# MCU021_V1_0_eZFET_DCDC.net
KiCad netlist of a schematic drawn in Altium Designer
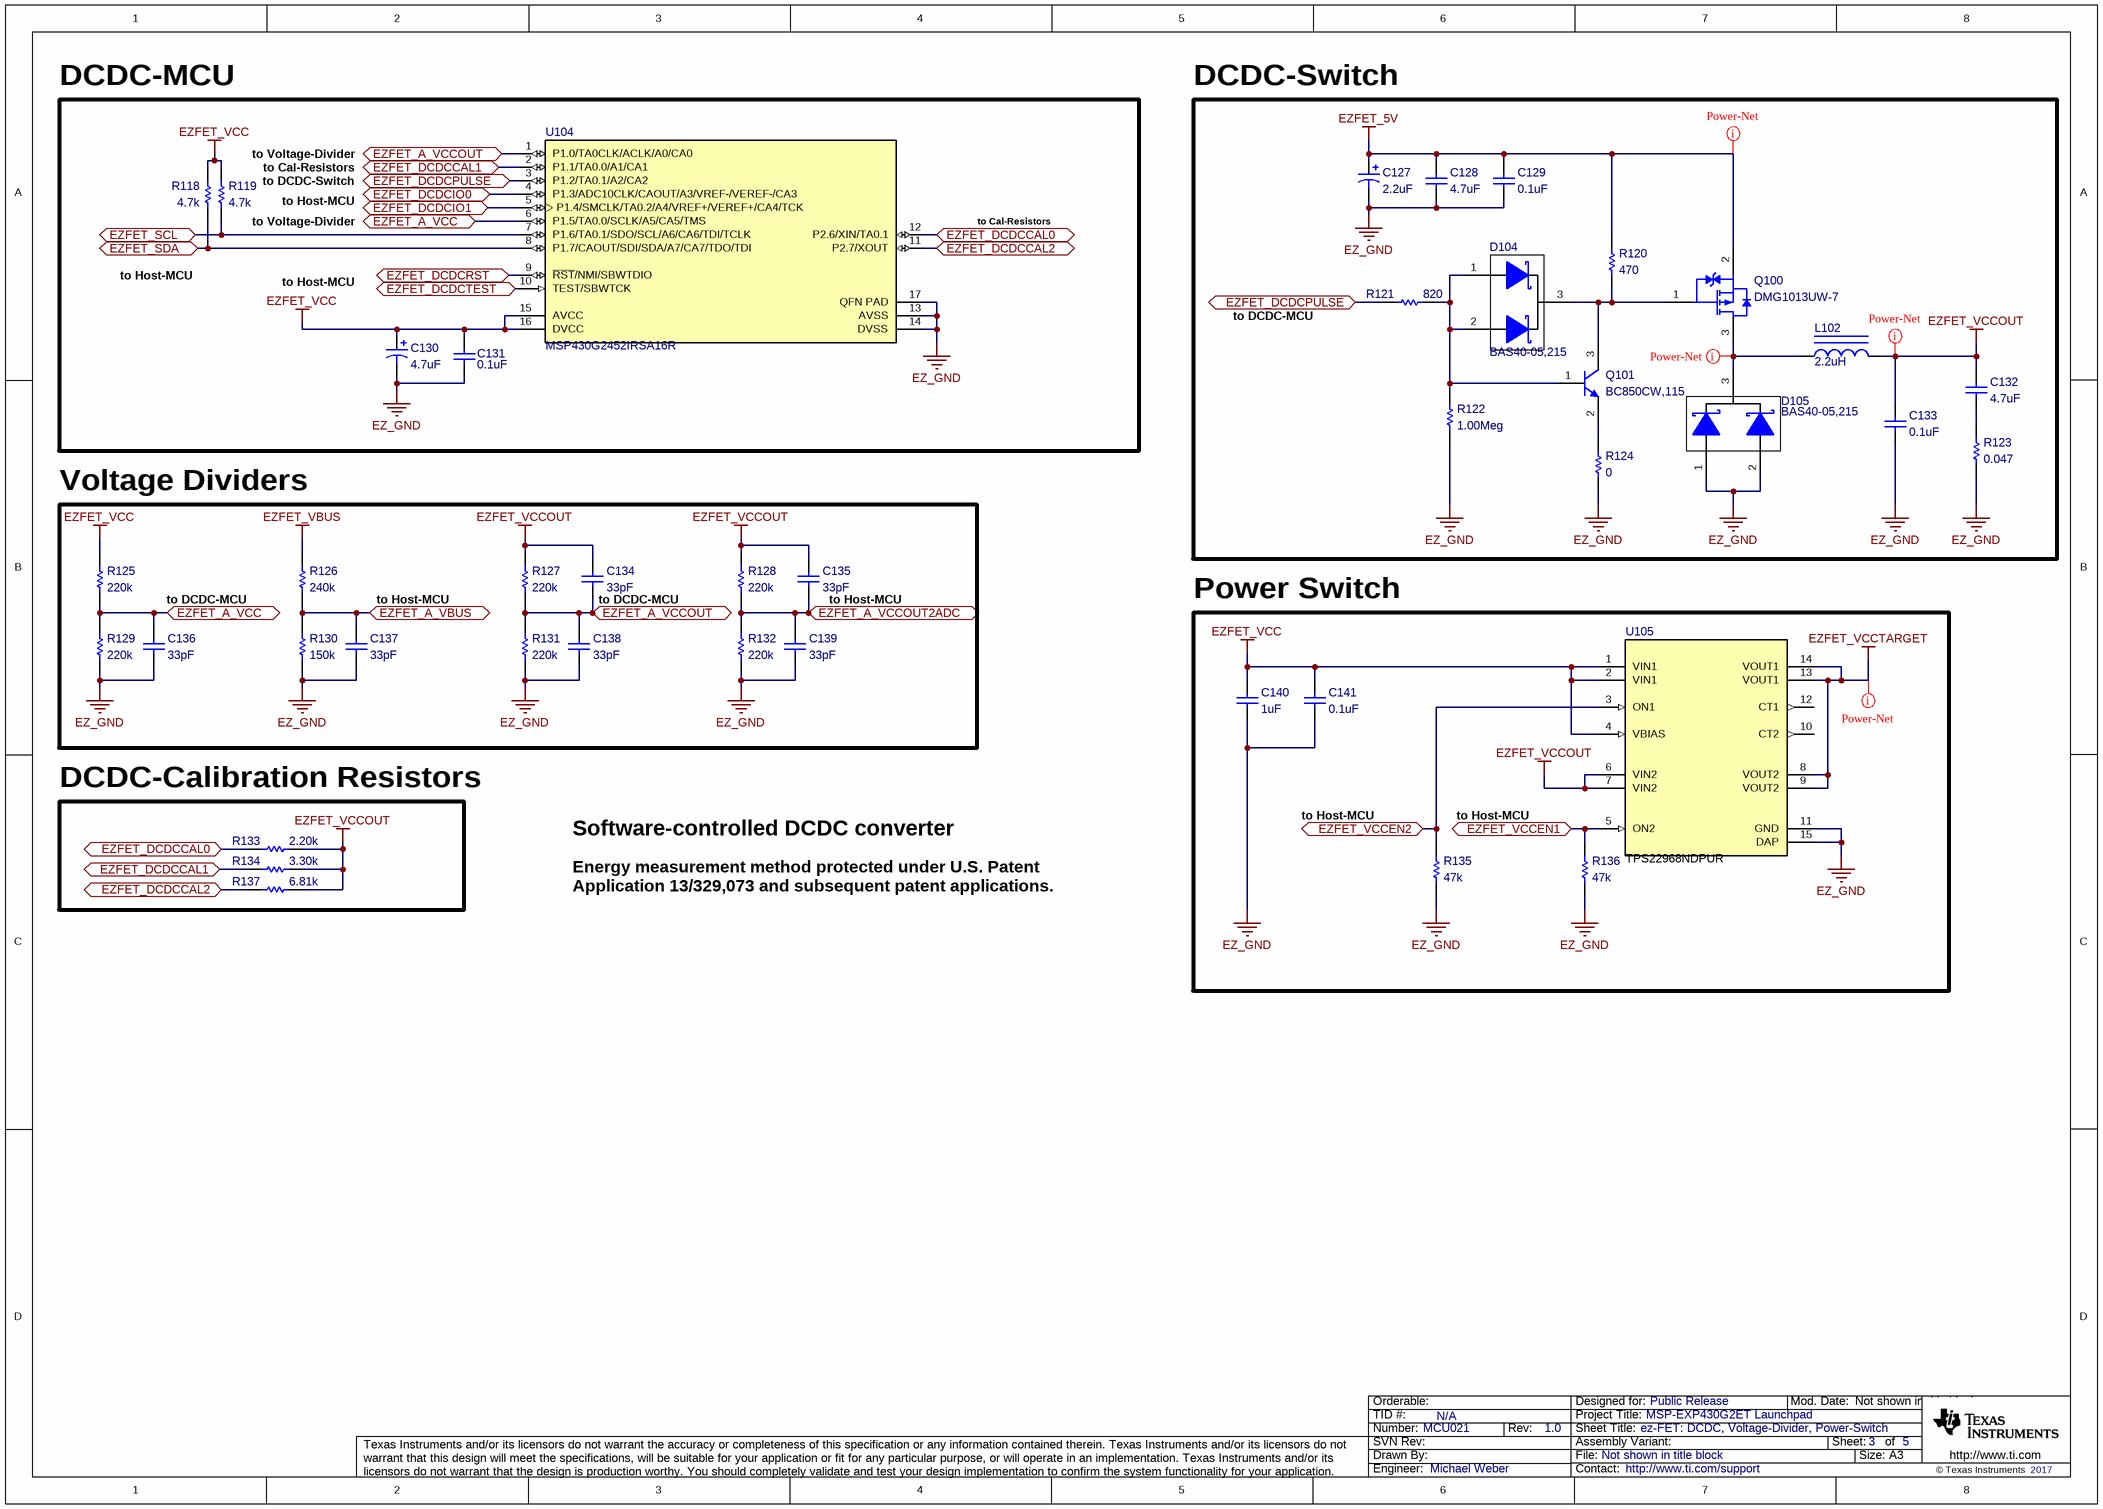
[diagram p0: MCU021_V1.0_eZFET_DCDC.SchDoc]

(export (version "E")
  (design (tool "Eeschema 10.0.6"))
  (components
    (comp (ref "C127")
      (value "2.2uF")
      (footprint "3216-18")
      (description "CAP, TA, 2.2 µF, 25 V, +/- 10%, 6.3 ohm, SMD")
      (fields
        (field (name "PARTNUMBER") "293D225X9025A2TE3")
        (field (name "MANUFACTURER") "Vishay-Sprague")
        (field (name "PUBLISHER") "Texas Instruments")
      )
      (libsource (lib "Capacitor_Tantalum") (part "293D225X9025A2TE3"))
    )
    (comp (ref "C128")
      (value "4.7uF")
      (footprint "0805_HV")
      (description "CAP, CERM, 4.7 µF, 10 V,+/- 10%, X5R, 0805")
      (fields
        (field (name "PARTNUMBER") "C0805C475K8PACTU")
        (field (name "MANUFACTURER") "Kemet")
        (field (name "PUBLISHER") "Texas Instruments")
      )
      (libsource (lib "Capacitor_Ceramic") (part "C0805C475K8PACTU"))
    )
    (comp (ref "C129")
      (value "0.1uF")
      (footprint "0402")
      (description "CAP, CERM, 0.1 µF, 10 V,+/- 10%, X5R, 0402")
      (fields
        (field (name "PARTNUMBER") "GRM155R61A104KA01D")
        (field (name "MANUFACTURER") "MuRata")
        (field (name "PUBLISHER") "Texas Instruments")
      )
      (libsource (lib "Capacitor_Ceramic") (part "GRM155R61A104KA01D"))
    )
    (comp (ref "C130")
      (value "4.7uF")
      (footprint "3216-18")
      (description "CAP, TA, 4.7 µF, 10 V, +/- 10%, 5 ohm, SMD")
      (fields
        (field (name "PARTNUMBER") "293D475X9010A2TE3")
        (field (name "MANUFACTURER") "Vishay-Sprague")
        (field (name "PUBLISHER") "Texas Instruments")
      )
      (libsource (lib "Capacitor_Tantalum") (part "293D475X9010A2TE3"))
    )
    (comp (ref "C131")
      (value "0.1uF")
      (footprint "0402")
      (description "CAP, CERM, 0.1 µF, 10 V,+/- 10%, X5R, 0402")
      (fields
        (field (name "PARTNUMBER") "GRM155R61A104KA01D")
        (field (name "MANUFACTURER") "MuRata")
        (field (name "PUBLISHER") "Texas Instruments")
      )
      (libsource (lib "Capacitor_Ceramic") (part "GRM155R61A104KA01D"))
    )
    (comp (ref "C132")
      (value "4.7uF")
      (footprint "0603")
      (description "CAP, CERM, 4.7 µF, 10 V,+/- 10%, X5R, 0603")
      (fields
        (field (name "PARTNUMBER") "CGB3B1X5R1A475K055AC")
        (field (name "MANUFACTURER") "TDK")
        (field (name "PUBLISHER") "Texas Instruments")
      )
      (libsource (lib "Capacitor_Ceramic") (part "CGB3B1X5R1A475K055AC"))
    )
    (comp (ref "C133")
      (value "0.1uF")
      (footprint "0402")
      (description "CAP, CERM, 0.1 µF, 10 V,+/- 10%, X5R, 0402")
      (fields
        (field (name "PARTNUMBER") "C1005X5R1A104K050BA")
        (field (name "MANUFACTURER") "TDK")
        (field (name "PUBLISHER") "Texas Instruments")
      )
      (libsource (lib "Capacitor_Ceramic") (part "C1005X5R1A104K050BA"))
    )
    (comp (ref "C134")
      (value "33pF")
      (footprint "0402")
      (description "CAP, CERM, 33 pF, 50 V,+/- 5%, C0G/NP0, 0402")
      (fields
        (field (name "PARTNUMBER") "C1005C0G1H330J050BA")
        (field (name "MANUFACTURER") "TDK")
        (field (name "PUBLISHER") "Texas Instruments")
      )
      (libsource (lib "Capacitor_Ceramic") (part "C1005C0G1H330J050BA"))
    )
    (comp (ref "C135")
      (value "33pF")
      (footprint "0402")
      (description "CAP, CERM, 33 pF, 50 V,+/- 5%, C0G/NP0, 0402")
      (fields
        (field (name "PARTNUMBER") "C1005C0G1H330J050BA")
        (field (name "MANUFACTURER") "TDK")
        (field (name "PUBLISHER") "Texas Instruments")
      )
      (libsource (lib "Capacitor_Ceramic") (part "C1005C0G1H330J050BA"))
    )
    (comp (ref "C136")
      (value "33pF")
      (footprint "0402")
      (description "CAP, CERM, 33 pF, 50 V,+/- 5%, C0G/NP0, 0402")
      (fields
        (field (name "PARTNUMBER") "C1005C0G1H330J050BA")
        (field (name "MANUFACTURER") "TDK")
        (field (name "PUBLISHER") "Texas Instruments")
      )
      (libsource (lib "Capacitor_Ceramic") (part "C1005C0G1H330J050BA"))
    )
    (comp (ref "C137")
      (value "33pF")
      (footprint "0402")
      (description "CAP, CERM, 33 pF, 50 V,+/- 5%, C0G/NP0, 0402")
      (fields
        (field (name "PARTNUMBER") "C1005C0G1H330J050BA")
        (field (name "MANUFACTURER") "TDK")
        (field (name "PUBLISHER") "Texas Instruments")
      )
      (libsource (lib "Capacitor_Ceramic") (part "C1005C0G1H330J050BA"))
    )
    (comp (ref "C138")
      (value "33pF")
      (footprint "0402")
      (description "CAP, CERM, 33 pF, 50 V,+/- 5%, C0G/NP0, 0402")
      (fields
        (field (name "PARTNUMBER") "C1005C0G1H330J050BA")
        (field (name "MANUFACTURER") "TDK")
        (field (name "PUBLISHER") "Texas Instruments")
      )
      (libsource (lib "Capacitor_Ceramic") (part "C1005C0G1H330J050BA"))
    )
    (comp (ref "C139")
      (value "33pF")
      (footprint "0402")
      (description "CAP, CERM, 33 pF, 50 V,+/- 5%, C0G/NP0, 0402")
      (fields
        (field (name "PARTNUMBER") "C1005C0G1H330J050BA")
        (field (name "MANUFACTURER") "TDK")
        (field (name "PUBLISHER") "Texas Instruments")
      )
      (libsource (lib "Capacitor_Ceramic") (part "C1005C0G1H330J050BA"))
    )
    (comp (ref "C140")
      (value "1uF")
      (footprint "0402")
      (description "CAP, CERM, 1 µF, 10 V,+/- 10%, X5R, 0402")
      (fields
        (field (name "PARTNUMBER") "GRM155R61A105KE15D")
        (field (name "MANUFACTURER") "MuRata")
        (field (name "PUBLISHER") "Texas Instruments")
      )
      (libsource (lib "Capacitor_Ceramic") (part "GRM155R61A105KE15D"))
    )
    (comp (ref "C141")
      (value "0.1uF")
      (footprint "0402")
      (description "CAP, CERM, 0.1 µF, 10 V,+/- 10%, X5R, 0402")
      (fields
        (field (name "PARTNUMBER") "GRM155R61A104KA01D")
        (field (name "MANUFACTURER") "MuRata")
        (field (name "PUBLISHER") "Texas Instruments")
      )
      (libsource (lib "Capacitor_Ceramic") (part "GRM155R61A104KA01D"))
    )
    (comp (ref "D104")
      (value "BAS40-05,215")
      (footprint "SOT-23")
      (description "Diode, Schottky, 40 V, 0.12 A, AEC-Q101, SOT-23")
      (fields
        (field (name "MANUFACTURER") "Nexperia")
        (field (name "SYMBOLCREATOR") "a0412235")
        (field (name "PUBLISHER") "Texas Instruments")
      )
      (libsource (lib "") (part "BAS40-05,215_1"))
    )
    (comp (ref "D105")
      (value "BAS40-05,215")
      (footprint "SOT-23")
      (description "Diode, Schottky, 40 V, 0.12 A, AEC-Q101, SOT-23")
      (fields
        (field (name "MANUFACTURER") "Nexperia")
        (field (name "SYMBOLCREATOR") "a0412235")
        (field (name "PUBLISHER") "Texas Instruments")
      )
      (libsource (lib "Diode") (part "BAS40-05,215"))
    )
    (comp (ref "L102")
      (value "2.2uH")
      (footprint "CBC2518")
      (description "Inductor, Wirewound, Ceramic, 2.2 µH, 0.89 A, 0.13 ohm, SMD")
      (fields
        (field (name "PARTNUMBER") "CBC2518T2R2M")
        (field (name "MANUFACTURER") "Taiyo Yuden")
        (field (name "PUBLISHER") "Texas Instruments")
      )
      (libsource (lib "Inductor_Other") (part "CBC2518T2R2M"))
    )
    (comp (ref "Q100")
      (value "DMG1013UW-7")
      (footprint "SOT-323")
      (description "MOSFET, P-CH, -20 V, -0.82 A, SOT-323")
      (fields
        (field (name "MANUFACTURER") "Diodes Inc.")
        (field (name "SYMBOLCREATOR") "a0411947")
        (field (name "PUBLISHER") "Texas Instruments")
      )
      (libsource (lib "FETs") (part "DMG1013UW-7"))
    )
    (comp (ref "Q101")
      (value "BC850CW,115")
      (footprint "SOT-323")
      (description "Transistor, NPN, 45 V, 0.1 A, SOT-323")
      (fields (field (name "MANUFACTURER") "Nexperia") (field (name "PUBLISHER") "Texas Instruments"))
      (libsource (lib "Bipolar_Transistor") (part "BC850CW,115, Nexperia"))
    )
    (comp (ref "R118")
      (value "4.7k")
      (footprint "0402")
      (description "RES, 4.7 k, 5%, 0.063 W, 0402")
      (fields
        (field (name "PARTNUMBER") "CRCW04024K70JNED")
        (field (name "MANUFACTURER") "Vishay-Dale")
        (field (name "PUBLISHER") "Texas Instruments")
      )
      (libsource (lib "Resistor_0402") (part "CRCW04024K70JNED"))
    )
    (comp (ref "R119")
      (value "4.7k")
      (footprint "0402")
      (description "RES, 4.7 k, 5%, 0.063 W, 0402")
      (fields
        (field (name "PARTNUMBER") "CRCW04024K70JNED")
        (field (name "MANUFACTURER") "Vishay-Dale")
        (field (name "PUBLISHER") "Texas Instruments")
      )
      (libsource (lib "Resistor_0402") (part "CRCW04024K70JNED"))
    )
    (comp (ref "R120")
      (value "470")
      (footprint "0402")
      (description "RES, 470, 1%, 0.063 W, 0402")
      (fields
        (field (name "PARTNUMBER") "RC0402FR-07470RL")
        (field (name "MANUFACTURER") "Yageo America")
        (field (name "PUBLISHER") "Texas Instruments")
      )
      (libsource (lib "Resistor_0402") (part "RC0402FR-07470RL"))
    )
    (comp (ref "R121")
      (value "820")
      (footprint "0402")
      (description "RES, 820, 1%, 0.063 W, 0402")
      (fields
        (field (name "PARTNUMBER") "RC0402FR-07820RL")
        (field (name "MANUFACTURER") "Yageo America")
        (field (name "PUBLISHER") "Texas Instruments")
      )
      (libsource (lib "Resistor_0402") (part "RC0402FR-07820RL"))
    )
    (comp (ref "R122")
      (value "1.00Meg")
      (footprint "0402")
      (description "RES, 1.00 M, 1%, 0.063 W, 0402")
      (fields
        (field (name "PARTNUMBER") "CRCW04021M00FKED")
        (field (name "MANUFACTURER") "Vishay-Dale")
        (field (name "PUBLISHER") "Texas Instruments")
      )
      (libsource (lib "Resistor_0402") (part "CRCW04021M00FKED"))
    )
    (comp (ref "R123")
      (value "0.047")
      (footprint "0603")
      (description "RES, 0.047, 1%, 0.1 W, 0603")
      (fields
        (field (name "PARTNUMBER") "ERJ-L03KF47MV")
        (field (name "MANUFACTURER") "Panasonic")
        (field (name "PUBLISHER") "Texas Instruments")
      )
      (libsource (lib "Resistor_0603") (part "ERJ-L03KF47MV"))
    )
    (comp (ref "R124")
      (value "0")
      (footprint "0402")
      (description "RES, 0, 5%, 0.063 W, 0402")
      (fields
        (field (name "PARTNUMBER") "RC0402JR-070RL")
        (field (name "MANUFACTURER") "Yageo America")
        (field (name "PUBLISHER") "Texas Instruments")
      )
      (libsource (lib "Resistor_0402") (part "RC0402JR-070RL"))
    )
    (comp (ref "R125")
      (value "220k")
      (footprint "0402")
      (description "RES, 220 k, 1%, 0.0625 W, 0402")
      (fields
        (field (name "PARTNUMBER") "RC0402FR-07220KL")
        (field (name "MANUFACTURER") "Yageo America")
        (field (name "PUBLISHER") "Texas Instruments")
      )
      (libsource (lib "Resistor_0402") (part "RC0402FR-07220KL"))
    )
    (comp (ref "R126")
      (value "240k")
      (footprint "0402")
      (description "RES, 240 k, 1%, 0.063 W, 0402")
      (fields
        (field (name "PARTNUMBER") "CRCW0402240KFKED")
        (field (name "MANUFACTURER") "Vishay-Dale")
        (field (name "PUBLISHER") "Texas Instruments")
      )
      (libsource (lib "Resistor_0402") (part "CRCW0402240KFKED"))
    )
    (comp (ref "R127")
      (value "220k")
      (footprint "0603")
      (description "RES, 220 k, 0.1%, 0.063 W, 0603")
      (fields
        (field (name "PARTNUMBER") "CPF0603B220KE")
        (field (name "MANUFACTURER") "TE Connectivity")
        (field (name "PUBLISHER") "Texas Instruments")
      )
      (libsource (lib "Resistor_0603") (part "CPF0603B220KE"))
    )
    (comp (ref "R128")
      (value "220k")
      (footprint "0603")
      (description "RES, 220 k, 0.1%, 0.063 W, 0603")
      (fields
        (field (name "PARTNUMBER") "CPF0603B220KE")
        (field (name "MANUFACTURER") "TE Connectivity")
        (field (name "PUBLISHER") "Texas Instruments")
      )
      (libsource (lib "Resistor_0603") (part "CPF0603B220KE"))
    )
    (comp (ref "R129")
      (value "220k")
      (footprint "0402")
      (description "RES, 220 k, 1%, 0.0625 W, 0402")
      (fields
        (field (name "PARTNUMBER") "RC0402FR-07220KL")
        (field (name "MANUFACTURER") "Yageo America")
        (field (name "PUBLISHER") "Texas Instruments")
      )
      (libsource (lib "Resistor_0402") (part "RC0402FR-07220KL"))
    )
    (comp (ref "R130")
      (value "150k")
      (footprint "0402")
      (description "RES, 150 k, 1%, 0.063 W, 0402")
      (fields
        (field (name "PARTNUMBER") "CRCW0402150KFKED")
        (field (name "MANUFACTURER") "Vishay-Dale")
        (field (name "PUBLISHER") "Texas Instruments")
      )
      (libsource (lib "Resistor_0402") (part "CRCW0402150KFKED"))
    )
    (comp (ref "R131")
      (value "220k")
      (footprint "0603")
      (description "RES, 220 k, 0.1%, 0.063 W, 0603")
      (fields
        (field (name "PARTNUMBER") "CPF0603B220KE")
        (field (name "MANUFACTURER") "TE Connectivity")
        (field (name "PUBLISHER") "Texas Instruments")
      )
      (libsource (lib "Resistor_0603") (part "CPF0603B220KE"))
    )
    (comp (ref "R132")
      (value "220k")
      (footprint "0603")
      (description "RES, 220 k, 0.1%, 0.063 W, 0603")
      (fields
        (field (name "PARTNUMBER") "CPF0603B220KE")
        (field (name "MANUFACTURER") "TE Connectivity")
        (field (name "PUBLISHER") "Texas Instruments")
      )
      (libsource (lib "Resistor_0603") (part "CPF0603B220KE"))
    )
    (comp (ref "R133")
      (value "2.20k")
      (footprint "0402")
      (description "RES, 2.20 k, 0.1%, 0.0625 W, AEC-Q200 Grade 0, 0402")
      (fields
        (field (name "PARTNUMBER") "ERA2AEB222X")
        (field (name "MANUFACTURER") "Panasonic")
        (field (name "PUBLISHER") "Texas Instruments")
      )
      (libsource (lib "Resistor_0402") (part "ERA2AEB222X"))
    )
    (comp (ref "R134")
      (value "3.30k")
      (footprint "0402")
      (description "RES, 3.30 k, 0.1%, 0.0625 W, AEC-Q200 Grade 0, 0402")
      (fields
        (field (name "PARTNUMBER") "ERA2ARB332X")
        (field (name "MANUFACTURER") "Panasonic")
        (field (name "PUBLISHER") "Texas Instruments")
      )
      (libsource (lib "Resistor_0402") (part "ERA2ARB332X"))
    )
    (comp (ref "R135")
      (value "47k")
      (footprint "0402")
      (description "RES, 47 k, 5%, 0.063 W, 0402")
      (fields
        (field (name "PARTNUMBER") "CRCW040247K0JNED")
        (field (name "MANUFACTURER") "Vishay-Dale")
        (field (name "PUBLISHER") "Texas Instruments")
      )
      (libsource (lib "Resistor_0402") (part "CRCW040247K0JNED"))
    )
    (comp (ref "R136")
      (value "47k")
      (footprint "0402")
      (description "RES, 47 k, 5%, 0.063 W, 0402")
      (fields
        (field (name "PARTNUMBER") "CRCW040247K0JNED")
        (field (name "MANUFACTURER") "Vishay-Dale")
        (field (name "PUBLISHER") "Texas Instruments")
      )
      (libsource (lib "Resistor_0402") (part "CRCW040247K0JNED"))
    )
    (comp (ref "R137")
      (value "6.81k")
      (footprint "0402")
      (description "RES, 6.81 k, 0.1%, 0.0625 W, AEC-Q200 Grade 0, 0402")
      (fields
        (field (name "PARTNUMBER") "ERA2AEB6811X")
        (field (name "MANUFACTURER") "Panasonic")
        (field (name "PUBLISHER") "Texas Instruments")
      )
      (libsource (lib "Resistor_0402") (part "ERA2AEB6811X"))
    )
    (comp (ref "U104")
      (value "MSP430G2452IRSA16R")
      (footprint "RSA0016B")
      (fields
        (field (name "ALTERNATE PARTNUMBER") "Equivalent")
        (field (name "MANUFACTURER") "Texas Instruments")
      )
      (libsource (lib "TI MCU MSP430") (part "MSP430G2452IRSA16R"))
    )
    (comp (ref "U105")
      (value "TPS22968NDPUR")
      (footprint "DPU0014A")
      (fields
        (field (name "MANUFACTURER") "Texas Instruments")
        (field (name "SYMBOLCREATOR") "a0411947")
        (field (name "PUBLISHER") "Texas Instruments")
      )
      (libsource (lib "TI_Pre_Release1") (part "TPS22968NDPUR"))
    )
  )
  (nets
    (net (code "1") (name "/EZFET_A_VBUS") (class "Default")
      (node (ref "C137") (pin "1") (pinfunction "1_1") (pintype "passive"))
      (node (ref "R126") (pin "1") (pinfunction "1_1") (pintype "passive"))
      (node (ref "R130") (pin "2") (pinfunction "2_2") (pintype "passive"))
    )
    (net (code "2") (name "/EZFET_A_VCC") (class "Default")
      (node (ref "C136") (pin "1") (pinfunction "1_1") (pintype "passive"))
      (node (ref "R125") (pin "1") (pinfunction "1_1") (pintype "passive"))
      (node (ref "R129") (pin "2") (pinfunction "2_2") (pintype "passive"))
      (node (ref "U104") (pin "6") (pinfunction "P1.5/TA0.0/SCLK/A5/CA5/TMS_6") (pintype "bidirectional"))
    )
    (net (code "3") (name "/EZFET_A_VCCOUT") (class "Default")
      (node (ref "C134") (pin "2") (pinfunction "2_2") (pintype "passive"))
      (node (ref "C138") (pin "1") (pinfunction "1_1") (pintype "passive"))
      (node (ref "R127") (pin "1") (pinfunction "1_1") (pintype "passive"))
      (node (ref "R131") (pin "2") (pinfunction "2_2") (pintype "passive"))
      (node (ref "U104") (pin "1") (pinfunction "P1.0/TA0CLK/ACLK/A0/CA0_1") (pintype "bidirectional"))
    )
    (net (code "4") (name "/EZFET_A_VCCOUT2ADC") (class "Default")
      (node (ref "C135") (pin "2") (pinfunction "2_2") (pintype "passive"))
      (node (ref "C139") (pin "1") (pinfunction "1_1") (pintype "passive"))
      (node (ref "R128") (pin "1") (pinfunction "1_1") (pintype "passive"))
      (node (ref "R132") (pin "2") (pinfunction "2_2") (pintype "passive"))
    )
    (net (code "5") (name "/EZFET_DCDCCAL0") (class "Default")
      (node (ref "R133") (pin "1") (pinfunction "1_1") (pintype "passive"))
      (node (ref "U104") (pin "12") (pinfunction "P2.6/XIN/TA0.1_12") (pintype "bidirectional"))
    )
    (net (code "6") (name "/EZFET_DCDCCAL1") (class "Default")
      (node (ref "R134") (pin "1") (pinfunction "1_1") (pintype "passive"))
      (node (ref "U104") (pin "2") (pinfunction "P1.1/TA0.0/A1/CA1_2") (pintype "bidirectional"))
    )
    (net (code "7") (name "/EZFET_DCDCCAL2") (class "Default")
      (node (ref "R137") (pin "1") (pinfunction "1_1") (pintype "passive"))
      (node (ref "U104") (pin "11") (pinfunction "P2.7/XOUT_11") (pintype "bidirectional"))
    )
    (net (code "8") (name "/EZFET_DCDCIO0") (class "Default")
      (node (ref "U104") (pin "4") (pinfunction "P1.3/ADC10CLK/CAOUT/A3/VREF-/VEREF-/CA3_4") (pintype "bidirectional"))
    )
    (net (code "9") (name "/EZFET_DCDCIO1") (class "Default")
      (node (ref "U104") (pin "5") (pinfunction "P1.4/SMCLK/TA0.2/A4/VREF+/VEREF+/CA4/TCK_5") (pintype "bidirectional"))
    )
    (net (code "10") (name "/EZFET_DCDCPULSE") (class "Default")
      (node (ref "R121") (pin "1") (pinfunction "1_1") (pintype "passive"))
      (node (ref "U104") (pin "3") (pinfunction "P1.2/TA0.1/A2/CA2_3") (pintype "bidirectional"))
    )
    (net (code "11") (name "/EZFET_DCDCRST") (class "Default")
      (node (ref "U104") (pin "9") (pinfunction "~{RST}/NMI/SBWTDIO_9") (pintype "bidirectional"))
    )
    (net (code "12") (name "/EZFET_DCDCTEST") (class "Default")
      (node (ref "U104") (pin "10") (pinfunction "TEST/SBWTCK_10") (pintype "input"))
    )
    (net (code "13") (name "/EZFET_SCL") (class "Default")
      (node (ref "R119") (pin "1") (pinfunction "1_1") (pintype "passive"))
      (node (ref "U104") (pin "7") (pinfunction "P1.6/TA0.1/SDO/SCL/A6/CA6/TDI/TCLK_7") (pintype "bidirectional"))
    )
    (net (code "14") (name "/EZFET_SDA") (class "Default")
      (node (ref "R118") (pin "1") (pinfunction "1_1") (pintype "passive"))
      (node (ref "U104") (pin "8") (pinfunction "P1.7/CAOUT/SDI/SDA/A7/CA7/TDO/TDI_8") (pintype "bidirectional"))
    )
    (net (code "15") (name "/EZFET_VCCEN1") (class "Default")
      (node (ref "R136") (pin "2") (pinfunction "2_2") (pintype "passive"))
      (node (ref "U105") (pin "5") (pinfunction "ON2_5") (pintype "input"))
    )
    (net (code "16") (name "/EZFET_VCCEN2") (class "Default")
      (node (ref "R135") (pin "2") (pinfunction "2_2") (pintype "passive"))
      (node (ref "U105") (pin "3") (pinfunction "ON1_3") (pintype "input"))
    )
    (net (code "17") (name "EZFET_5V") (class "Default")
      (node (ref "C127") (pin "1") (pinfunction "+_1") (pintype "passive"))
      (node (ref "C128") (pin "1") (pinfunction "1_1") (pintype "passive"))
      (node (ref "C129") (pin "1") (pinfunction "1_1") (pintype "passive"))
      (node (ref "Q100") (pin "2") (pinfunction "S_2") (pintype "passive"))
      (node (ref "R120") (pin "2") (pinfunction "2_2") (pintype "passive"))
    )
    (net (code "18") (name "EZFET_VBUS") (class "Default")
      (node (ref "R126") (pin "2") (pinfunction "2_2") (pintype "passive"))
    )
    (net (code "19") (name "EZFET_VCC") (class "Default")
      (node (ref "C130") (pin "1") (pinfunction "+_1") (pintype "passive"))
      (node (ref "C131") (pin "1") (pinfunction "1_1") (pintype "passive"))
      (node (ref "C140") (pin "1") (pinfunction "1_1") (pintype "passive"))
      (node (ref "C141") (pin "2") (pinfunction "2_2") (pintype "passive"))
      (node (ref "R118") (pin "2") (pinfunction "2_2") (pintype "passive"))
      (node (ref "R119") (pin "2") (pinfunction "2_2") (pintype "passive"))
      (node (ref "R125") (pin "2") (pinfunction "2_2") (pintype "passive"))
      (node (ref "U104") (pin "15") (pinfunction "AVCC_15") (pintype "power_in"))
      (node (ref "U104") (pin "16") (pinfunction "DVCC_16") (pintype "power_in"))
      (node (ref "U105") (pin "1") (pinfunction "VIN1_1") (pintype "power_in"))
      (node (ref "U105") (pin "2") (pinfunction "VIN1_2") (pintype "power_in"))
      (node (ref "U105") (pin "4") (pinfunction "VBIAS_4") (pintype "input"))
    )
    (net (code "20") (name "EZFET_VCCOUT") (class "Default")
      (node (ref "C132") (pin "1") (pinfunction "1_1") (pintype "passive"))
      (node (ref "C133") (pin "1") (pinfunction "1_1") (pintype "passive"))
      (node (ref "C134") (pin "1") (pinfunction "1_1") (pintype "passive"))
      (node (ref "C135") (pin "1") (pinfunction "1_1") (pintype "passive"))
      (node (ref "L102") (pin "2") (pinfunction "2_2") (pintype "passive"))
      (node (ref "R127") (pin "2") (pinfunction "2_2") (pintype "passive"))
      (node (ref "R128") (pin "2") (pinfunction "2_2") (pintype "passive"))
      (node (ref "R133") (pin "2") (pinfunction "2_2") (pintype "passive"))
      (node (ref "R134") (pin "2") (pinfunction "2_2") (pintype "passive"))
      (node (ref "R137") (pin "2") (pinfunction "2_2") (pintype "passive"))
      (node (ref "U105") (pin "6") (pinfunction "VIN2_6") (pintype "power_in"))
      (node (ref "U105") (pin "7") (pinfunction "VIN2_7") (pintype "power_in"))
    )
    (net (code "21") (name "EZFET_VCCTARGET") (class "Default")
      (node (ref "U105") (pin "13") (pinfunction "VOUT1_13") (pintype "power_in"))
      (node (ref "U105") (pin "14") (pinfunction "VOUT1_14") (pintype "power_in"))
      (node (ref "U105") (pin "8") (pinfunction "VOUT2_8") (pintype "power_in"))
      (node (ref "U105") (pin "9") (pinfunction "VOUT2_9") (pintype "power_in"))
    )
    (net (code "22") (name "EZ_GND") (class "Default")
      (node (ref "C127") (pin "2") (pinfunction "-_2") (pintype "passive"))
      (node (ref "C128") (pin "2") (pinfunction "2_2") (pintype "passive"))
      (node (ref "C129") (pin "2") (pinfunction "2_2") (pintype "passive"))
      (node (ref "C130") (pin "2") (pinfunction "-_2") (pintype "passive"))
      (node (ref "C131") (pin "2") (pinfunction "2_2") (pintype "passive"))
      (node (ref "C133") (pin "2") (pinfunction "2_2") (pintype "passive"))
      (node (ref "C136") (pin "2") (pinfunction "2_2") (pintype "passive"))
      (node (ref "C137") (pin "2") (pinfunction "2_2") (pintype "passive"))
      (node (ref "C138") (pin "2") (pinfunction "2_2") (pintype "passive"))
      (node (ref "C139") (pin "2") (pinfunction "2_2") (pintype "passive"))
      (node (ref "C140") (pin "2") (pinfunction "2_2") (pintype "passive"))
      (node (ref "C141") (pin "1") (pinfunction "1_1") (pintype "passive"))
      (node (ref "D105") (pin "1") (pinfunction "A_1") (pintype "passive"))
      (node (ref "D105") (pin "2") (pinfunction "A_2") (pintype "passive"))
      (node (ref "R122") (pin "1") (pinfunction "1_1") (pintype "passive"))
      (node (ref "R123") (pin "1") (pinfunction "1_1") (pintype "passive"))
      (node (ref "R124") (pin "1") (pinfunction "1_1") (pintype "passive"))
      (node (ref "R129") (pin "1") (pinfunction "1_1") (pintype "passive"))
      (node (ref "R130") (pin "1") (pinfunction "1_1") (pintype "passive"))
      (node (ref "R131") (pin "1") (pinfunction "1_1") (pintype "passive"))
      (node (ref "R132") (pin "1") (pinfunction "1_1") (pintype "passive"))
      (node (ref "R135") (pin "1") (pinfunction "1_1") (pintype "passive"))
      (node (ref "R136") (pin "1") (pinfunction "1_1") (pintype "passive"))
      (node (ref "U104") (pin "13") (pinfunction "AVSS_13") (pintype "power_in"))
      (node (ref "U104") (pin "14") (pinfunction "DVSS_14") (pintype "power_in"))
      (node (ref "U104") (pin "17") (pinfunction "QFN_PAD_17") (pintype "power_in"))
      (node (ref "U105") (pin "11") (pinfunction "GND_11") (pintype "power_in"))
      (node (ref "U105") (pin "15") (pinfunction "DAP_15") (pintype "power_in"))
    )
    (net (code "23") (name "Net-(C132-Pad2)") (class "Default")
      (node (ref "C132") (pin "2") (pinfunction "2_2") (pintype "passive"))
      (node (ref "R123") (pin "2") (pinfunction "2_2") (pintype "passive"))
    )
    (net (code "24") (name "Net-(D104-K)") (class "Default")
      (node (ref "D104") (pin "3") (pinfunction "K_3") (pintype "passive"))
      (node (ref "Q100") (pin "1") (pinfunction "G_1") (pintype "passive"))
      (node (ref "Q101") (pin "3") (pinfunction "C_3") (pintype "passive"))
      (node (ref "R120") (pin "1") (pinfunction "1_1") (pintype "passive"))
    )
    (net (code "25") (name "Net-(D105-K)") (class "Default")
      (node (ref "D105") (pin "3") (pinfunction "K_3") (pintype "passive"))
      (node (ref "L102") (pin "1") (pinfunction "1_1") (pintype "passive"))
      (node (ref "Q100") (pin "3") (pinfunction "D_3") (pintype "passive"))
    )
    (net (code "26") (name "Net-(Q101-B)") (class "Default")
      (node (ref "D104") (pin "1") (pinfunction "A_1") (pintype "passive"))
      (node (ref "D104") (pin "2") (pinfunction "A_2") (pintype "passive"))
      (node (ref "Q101") (pin "1") (pinfunction "B_1") (pintype "passive"))
      (node (ref "R121") (pin "2") (pinfunction "2_2") (pintype "passive"))
      (node (ref "R122") (pin "2") (pinfunction "2_2") (pintype "passive"))
    )
    (net (code "27") (name "Net-(Q101-E)") (class "Default")
      (node (ref "Q101") (pin "2") (pinfunction "E_2") (pintype "passive"))
      (node (ref "R124") (pin "2") (pinfunction "2_2") (pintype "passive"))
    )
    (net (code "28") (name "unconnected-(U105-CT1-Pad12)") (class "Default")
      (node (ref "U105") (pin "12") (pinfunction "CT1_12") (pintype "output"))
    )
    (net (code "29") (name "unconnected-(U105-CT2-Pad10)") (class "Default")
      (node (ref "U105") (pin "10") (pinfunction "CT2_10") (pintype "output"))
    )
  )
)
